# MCU.net
KiCad netlist of a schematic drawn in Altium Designer
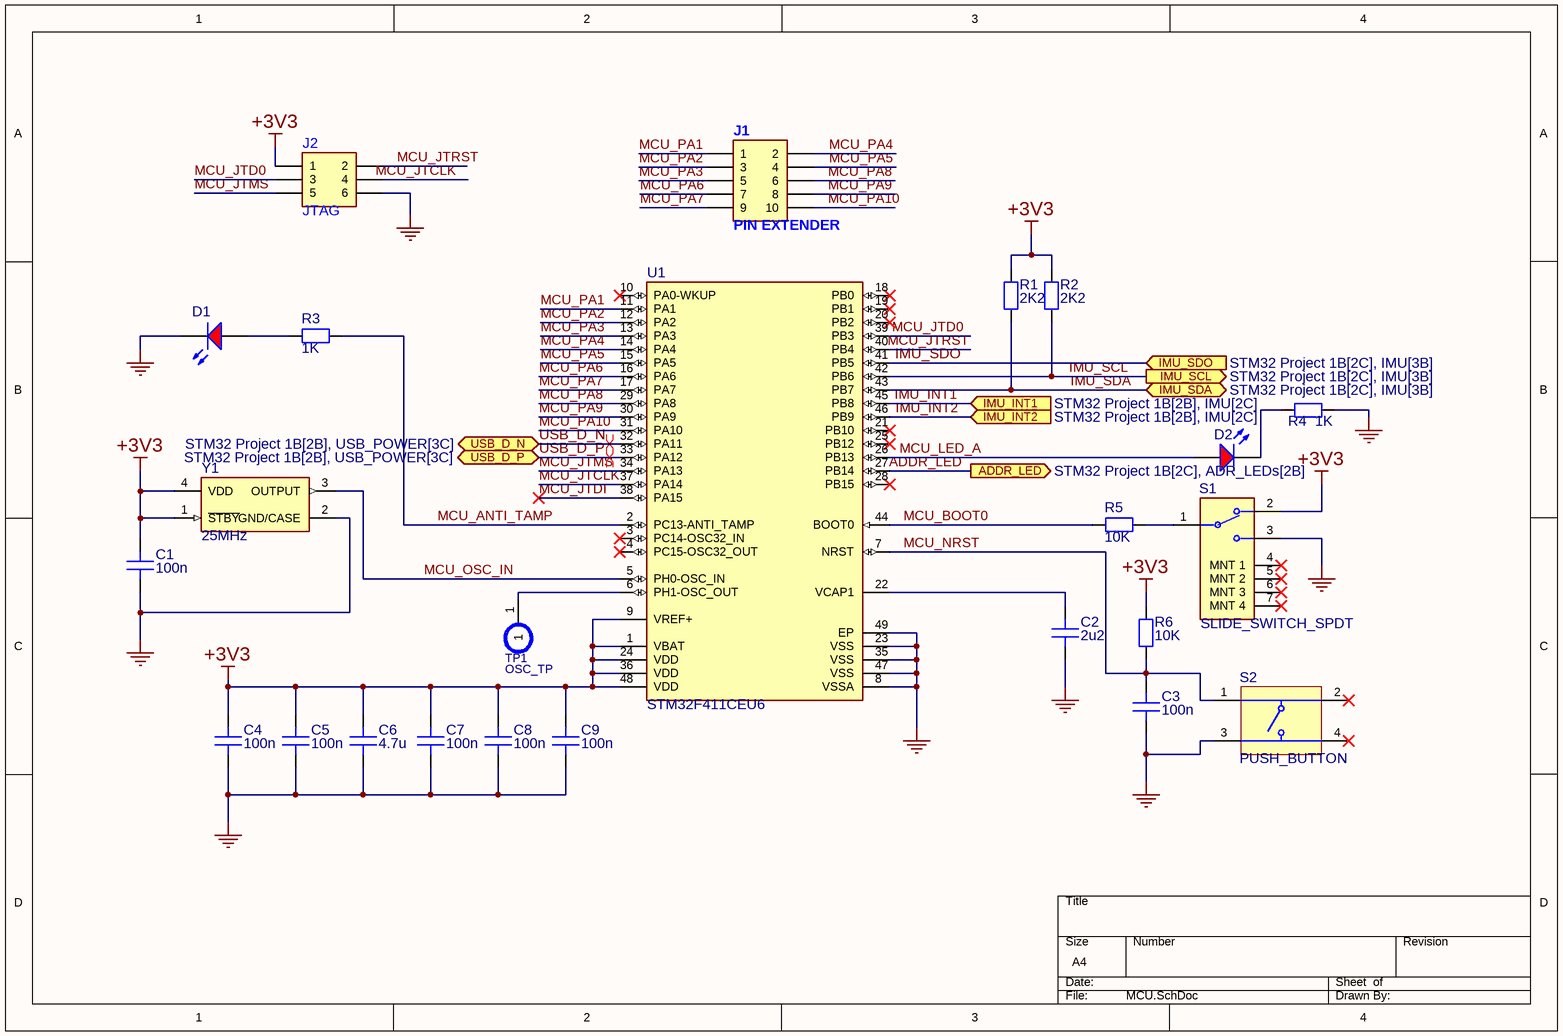
[diagram p0: MCU.SchDoc]

(export (version "E")
  (design (tool "Eeschema 10.0.6"))
  (components
    (comp (ref "C1")
      (value "100n")
      (footprint "CAP_0805")
      (description "Capacitor SMD 0805 Generic")
      (libsource (lib "Generic-Schematic-Library") (part "CAP_0805"))
    )
    (comp (ref "C2")
      (value "2u2")
      (footprint "CAP_0805")
      (description "Capacitor SMD 0805 Generic")
      (libsource (lib "Generic-Schematic-Library") (part "CAP_0805"))
    )
    (comp (ref "C3")
      (value "100n")
      (footprint "CAP_0805")
      (description "Capacitor SMD 0805 Generic")
      (libsource (lib "Generic-Schematic-Library") (part "CAP_0805"))
    )
    (comp (ref "C4")
      (value "100n")
      (footprint "CAP_0805")
      (description "Capacitor SMD 0805 Generic")
      (libsource (lib "Generic-Schematic-Library") (part "CAP_0805"))
    )
    (comp (ref "C5")
      (value "100n")
      (footprint "CAP_0805")
      (description "Capacitor SMD 0805 Generic")
      (libsource (lib "Generic-Schematic-Library") (part "CAP_0805"))
    )
    (comp (ref "C6")
      (value "4.7u")
      (footprint "CAP_0805")
      (description "Capacitor SMD 0805 Generic")
      (libsource (lib "Generic-Schematic-Library") (part "CAP_0805"))
    )
    (comp (ref "C7")
      (value "100n")
      (footprint "CAP_0805")
      (description "Capacitor SMD 0805 Generic")
      (libsource (lib "Generic-Schematic-Library") (part "CAP_0805"))
    )
    (comp (ref "C8")
      (value "100n")
      (footprint "CAP_0805")
      (description "Capacitor SMD 0805 Generic")
      (libsource (lib "Generic-Schematic-Library") (part "CAP_0805"))
    )
    (comp (ref "C9")
      (value "100n")
      (footprint "CAP_0805")
      (description "Capacitor SMD 0805 Generic")
      (libsource (lib "Generic-Schematic-Library") (part "CAP_0805"))
    )
    (comp (ref "D1")
      (value "LED_RED_0805")
      (footprint "LED_RED_0805")
      (description "Chip LED, Green, 2.2 V, -40 to 85 degC, 2-Pin SMD, Pb-Free, Tape and Reel")
      (libsource (lib "Generic-Schematic-Library") (part "LED_RED_0805"))
    )
    (comp (ref "D2")
      (value "LED_RED_0805")
      (footprint "LED_RED_0805")
      (description "Chip LED, Green, 2.2 V, -40 to 85 degC, 2-Pin SMD, Pb-Free, Tape and Reel")
      (libsource (lib "Generic-Schematic-Library") (part "LED_RED_0805"))
    )
    (comp (ref "J1")
      (value "PIN EXTENDER")
      (footprint "10P_2x5_HEADER")
      (description "10 Position SMD Pin Header 2x5")
      (libsource (lib "Generic-Schematic-Library") (part "10P_2x5_HEADER"))
    )
    (comp (ref "J2")
      (value "JTAG")
      (footprint "6P_2x3_HEADER")
      (description "Male Header, Pitch 2.54 mm, 2 x 3 Position, Height 8.13 mm, -65 to 125 degC, RoHS, Tube")
      (libsource (lib "Generic-Schematic-Library") (part "6P_2x3_HEADER"))
    )
    (comp (ref "R1")
      (value "2K2")
      (footprint "RES_0805")
      (description "Resistor SMD 0805 Generic")
      (libsource (lib "Generic-Schematic-Library") (part "RES_0805"))
    )
    (comp (ref "R2")
      (value "2K2")
      (footprint "RES_0805")
      (description "Resistor SMD 0805 Generic")
      (libsource (lib "Generic-Schematic-Library") (part "RES_0805"))
    )
    (comp (ref "R3")
      (value "1K")
      (footprint "RES_0805")
      (description "Resistor SMD 0805 Generic")
      (libsource (lib "Generic-Schematic-Library") (part "RES_0805"))
    )
    (comp (ref "R4")
      (value "1K")
      (footprint "RES_0805")
      (description "Resistor SMD 0805 Generic")
      (libsource (lib "Generic-Schematic-Library") (part "RES_0805"))
    )
    (comp (ref "R5")
      (value "10K")
      (footprint "RES_0805")
      (description "Resistor SMD 0805 Generic")
      (libsource (lib "Generic-Schematic-Library") (part "RES_0805"))
    )
    (comp (ref "R6")
      (value "10K")
      (footprint "RES_0805")
      (description "Resistor SMD 0805 Generic")
      (libsource (lib "Generic-Schematic-Library") (part "RES_0805"))
    )
    (comp (ref "S1")
      (value "SLIDE_SWITCH_SPDT")
      (footprint "SLIDE_SWITCH_SPDT")
      (description "SWITCH SLIDE SPDT 300MA 6V")
      (libsource (lib "Generic-Schematic-Library") (part "SLIDE_SWITCH_SPDT"))
    )
    (comp (ref "S2")
      (value "PUSH_BUTTON")
      (footprint "PUSH_BUTTON")
      (description "Micro Miniature Push Button Switch FSM JSM, 50 mA, -35 to 85 degC, 4-Pin SMD, RoHS, Tape and Reel")
      (fields (field (name "MANUFACTURER") "TE Connectivity"))
      (libsource (lib "Generic-Schematic-Library") (part "PUSH_BUTTON"))
    )
    (comp (ref "TP1")
      (value "OSC_TP")
      (footprint "TEST_POINT_SMD")
      (description "Test Point SMD Generic - for in circuit test")
      (libsource (lib "Generic-Schematic-Library") (part "TEST_POINT_SMD"))
    )
    (comp (ref "U1")
      (value "STM32F411CEU6")
      (footprint "STM32F411CEU6")
      (libsource (lib "Generic-Schematic-Library") (part "STM32F411CEU6"))
    )
    (comp (ref "Y1")
      (value "25MHz")
      (footprint "XTAL_OSCILLATOR_25MHz")
      (description "XTAL Oscillator 25MHz ±50ppm CMOS 3.3V 4-SMD 3.2mm x 2.5mm")
      (libsource (lib "Generic-Schematic-Library") (part "XTAL_OSCILLATOR_25MHz"))
    )
  )
  (nets
    (net (code "1") (name "+3V3") (class "Default")
      (node (ref "C1") (pin "2") (pintype "passive"))
      (node (ref "C4") (pin "2") (pintype "passive"))
      (node (ref "C5") (pin "2") (pintype "passive"))
      (node (ref "C6") (pin "2") (pintype "passive"))
      (node (ref "C7") (pin "2") (pintype "passive"))
      (node (ref "C8") (pin "2") (pintype "passive"))
      (node (ref "C9") (pin "2") (pintype "passive"))
      (node (ref "J2") (pin "1") (pinfunction "1_1") (pintype "passive"))
      (node (ref "R1") (pin "1") (pintype "passive"))
      (node (ref "R2") (pin "1") (pintype "passive"))
      (node (ref "R6") (pin "1") (pintype "passive"))
      (node (ref "S1") (pin "2") (pinfunction "2_2") (pintype "passive"))
      (node (ref "U1") (pin "1") (pinfunction "VBAT_1") (pintype "power_in"))
      (node (ref "U1") (pin "24") (pinfunction "VDD_24") (pintype "power_in"))
      (node (ref "U1") (pin "36") (pinfunction "VDD_36") (pintype "power_in"))
      (node (ref "U1") (pin "48") (pinfunction "VDD_48") (pintype "power_in"))
      (node (ref "U1") (pin "9") (pinfunction "VREF+_9") (pintype "power_in"))
      (node (ref "Y1") (pin "1") (pinfunction "~{STBY}_1") (pintype "input"))
      (node (ref "Y1") (pin "4") (pinfunction "VDD_4") (pintype "power_in"))
    )
    (net (code "2") (name "/ADDR_LED") (class "Default")
      (node (ref "U1") (pin "27") (pinfunction "PB14_27") (pintype "bidirectional"))
    )
    (net (code "3") (name "/IMU_INT1") (class "Default")
      (node (ref "U1") (pin "45") (pinfunction "PB8_45") (pintype "bidirectional"))
    )
    (net (code "4") (name "/IMU_INT2") (class "Default")
      (node (ref "U1") (pin "46") (pinfunction "PB9_46") (pintype "bidirectional"))
    )
    (net (code "5") (name "/IMU_SCL") (class "Default")
      (node (ref "R2") (pin "2") (pintype "passive"))
      (node (ref "U1") (pin "42") (pinfunction "PB6_42") (pintype "bidirectional"))
    )
    (net (code "6") (name "/IMU_SDA") (class "Default")
      (node (ref "R1") (pin "2") (pintype "passive"))
      (node (ref "U1") (pin "43") (pinfunction "PB7_43") (pintype "bidirectional"))
    )
    (net (code "7") (name "/IMU_SDO") (class "Default")
      (node (ref "U1") (pin "41") (pinfunction "PB5_41") (pintype "bidirectional"))
    )
    (net (code "8") (name "/MCU_ANTI_TAMP") (class "Default")
      (node (ref "R3") (pin "1") (pintype "passive"))
      (node (ref "U1") (pin "2") (pinfunction "PC13-ANTI_TAMP_2") (pintype "bidirectional"))
    )
    (net (code "9") (name "/MCU_BOOT0") (class "Default")
      (node (ref "R5") (pin "2") (pintype "passive"))
      (node (ref "U1") (pin "44") (pinfunction "BOOT0_44") (pintype "input"))
    )
    (net (code "10") (name "/MCU_JTCLK") (class "Default")
      (node (ref "J2") (pin "4") (pinfunction "4_4") (pintype "passive"))
      (node (ref "U1") (pin "37") (pinfunction "PA14_37") (pintype "bidirectional"))
    )
    (net (code "11") (name "/MCU_JTD0") (class "Default")
      (node (ref "J2") (pin "3") (pinfunction "3_3") (pintype "passive"))
      (node (ref "U1") (pin "39") (pinfunction "PB3_39") (pintype "bidirectional"))
    )
    (net (code "12") (name "/MCU_JTDI") (class "Default")
      (node (ref "U1") (pin "38") (pinfunction "PA15_38") (pintype "bidirectional+no_connect"))
    )
    (net (code "13") (name "/MCU_JTMS") (class "Default")
      (node (ref "J2") (pin "5") (pinfunction "5_5") (pintype "passive"))
      (node (ref "U1") (pin "34") (pinfunction "PA13_34") (pintype "bidirectional"))
    )
    (net (code "14") (name "/MCU_JTRST") (class "Default")
      (node (ref "J2") (pin "2") (pinfunction "2_2") (pintype "passive"))
      (node (ref "U1") (pin "40") (pinfunction "PB4_40") (pintype "bidirectional"))
    )
    (net (code "15") (name "/MCU_LED_A") (class "Default")
      (node (ref "D2") (pin "2") (pinfunction "A_2") (pintype "passive"))
      (node (ref "U1") (pin "26") (pinfunction "PB13_26") (pintype "bidirectional"))
    )
    (net (code "16") (name "/MCU_NRST") (class "Default")
      (node (ref "C3") (pin "2") (pintype "passive"))
      (node (ref "R6") (pin "2") (pintype "passive"))
      (node (ref "S2") (pin "1") (pinfunction "1_1") (pintype "passive"))
      (node (ref "U1") (pin "7") (pinfunction "NRST_7") (pintype "bidirectional"))
    )
    (net (code "17") (name "/MCU_OSC_IN") (class "Default")
      (node (ref "U1") (pin "5") (pinfunction "PH0-OSC_IN_5") (pintype "bidirectional"))
      (node (ref "Y1") (pin "3") (pinfunction "OUTPUT_3") (pintype "output"))
    )
    (net (code "18") (name "/MCU_PA1") (class "Default")
      (node (ref "J1") (pin "1") (pinfunction "1_1") (pintype "passive"))
      (node (ref "U1") (pin "11") (pinfunction "PA1_11") (pintype "bidirectional"))
    )
    (net (code "19") (name "/MCU_PA2") (class "Default")
      (node (ref "J1") (pin "3") (pinfunction "3_3") (pintype "passive"))
      (node (ref "U1") (pin "12") (pinfunction "PA2_12") (pintype "bidirectional"))
    )
    (net (code "20") (name "/MCU_PA3") (class "Default")
      (node (ref "J1") (pin "5") (pinfunction "5_5") (pintype "passive"))
      (node (ref "U1") (pin "13") (pinfunction "PA3_13") (pintype "bidirectional"))
    )
    (net (code "21") (name "/MCU_PA4") (class "Default")
      (node (ref "J1") (pin "2") (pinfunction "2_2") (pintype "passive"))
      (node (ref "U1") (pin "14") (pinfunction "PA4_14") (pintype "bidirectional"))
    )
    (net (code "22") (name "/MCU_PA5") (class "Default")
      (node (ref "J1") (pin "4") (pinfunction "4_4") (pintype "passive"))
      (node (ref "U1") (pin "15") (pinfunction "PA5_15") (pintype "bidirectional"))
    )
    (net (code "23") (name "/MCU_PA6") (class "Default")
      (node (ref "J1") (pin "7") (pinfunction "7_7") (pintype "passive"))
      (node (ref "U1") (pin "16") (pinfunction "PA6_16") (pintype "bidirectional"))
    )
    (net (code "24") (name "/MCU_PA7") (class "Default")
      (node (ref "J1") (pin "9") (pinfunction "9_9") (pintype "passive"))
      (node (ref "U1") (pin "17") (pinfunction "PA7_17") (pintype "bidirectional"))
    )
    (net (code "25") (name "/MCU_PA8") (class "Default")
      (node (ref "J1") (pin "6") (pinfunction "6_6") (pintype "passive"))
      (node (ref "U1") (pin "29") (pinfunction "PA8_29") (pintype "bidirectional"))
    )
    (net (code "26") (name "/MCU_PA9") (class "Default")
      (node (ref "J1") (pin "8") (pinfunction "8_8") (pintype "passive"))
      (node (ref "U1") (pin "30") (pinfunction "PA9_30") (pintype "bidirectional"))
    )
    (net (code "27") (name "/MCU_PA10") (class "Default")
      (node (ref "J1") (pin "10") (pinfunction "10_10") (pintype "passive"))
      (node (ref "U1") (pin "31") (pinfunction "PA10_31") (pintype "bidirectional"))
    )
    (net (code "28") (name "/USB_D_N") (class "Default")
      (node (ref "U1") (pin "32") (pinfunction "PA11_32") (pintype "bidirectional"))
    )
    (net (code "29") (name "/USB_D_P") (class "Default")
      (node (ref "U1") (pin "33") (pinfunction "PA12_33") (pintype "bidirectional"))
    )
    (net (code "30") (name "GND") (class "Default")
      (node (ref "C1") (pin "1") (pintype "passive"))
      (node (ref "C2") (pin "1") (pintype "passive"))
      (node (ref "C3") (pin "1") (pintype "passive"))
      (node (ref "C4") (pin "1") (pintype "passive"))
      (node (ref "C5") (pin "1") (pintype "passive"))
      (node (ref "C6") (pin "1") (pintype "passive"))
      (node (ref "C7") (pin "1") (pintype "passive"))
      (node (ref "C8") (pin "1") (pintype "passive"))
      (node (ref "C9") (pin "1") (pintype "passive"))
      (node (ref "D1") (pin "1") (pinfunction "K_1") (pintype "passive"))
      (node (ref "J2") (pin "6") (pinfunction "6_6") (pintype "passive"))
      (node (ref "R4") (pin "1") (pintype "passive"))
      (node (ref "S1") (pin "3") (pinfunction "3_3") (pintype "passive"))
      (node (ref "S2") (pin "3") (pinfunction "3_3") (pintype "passive"))
      (node (ref "U1") (pin "23") (pinfunction "VSS_23") (pintype "power_in"))
      (node (ref "U1") (pin "35") (pinfunction "VSS_35") (pintype "power_in"))
      (node (ref "U1") (pin "47") (pinfunction "VSS_47") (pintype "power_in"))
      (node (ref "U1") (pin "49") (pinfunction "EP_49") (pintype "power_in"))
      (node (ref "U1") (pin "8") (pinfunction "VSSA_8") (pintype "power_in"))
      (node (ref "Y1") (pin "2") (pinfunction "GND/CASE_2") (pintype "power_in"))
    )
    (net (code "31") (name "Net-(D1-A)") (class "Default")
      (node (ref "D1") (pin "2") (pinfunction "A_2") (pintype "passive"))
      (node (ref "R3") (pin "2") (pintype "passive"))
    )
    (net (code "32") (name "Net-(D2-K)") (class "Default")
      (node (ref "D2") (pin "1") (pinfunction "K_1") (pintype "passive"))
      (node (ref "R4") (pin "2") (pintype "passive"))
    )
    (net (code "33") (name "Net-(R5-Pad1)") (class "Default")
      (node (ref "R5") (pin "1") (pintype "passive"))
      (node (ref "S1") (pin "1") (pinfunction "1_1") (pintype "passive"))
    )
    (net (code "34") (name "Net-(U1-PH1-OSC_OUT)") (class "Default")
      (node (ref "TP1") (pin "1") (pinfunction "1_1") (pintype "passive"))
      (node (ref "U1") (pin "6") (pinfunction "PH1-OSC_OUT_6") (pintype "bidirectional"))
    )
    (net (code "35") (name "Net-(U1-VCAP1)") (class "Default")
      (node (ref "C2") (pin "2") (pintype "passive"))
      (node (ref "U1") (pin "22") (pinfunction "VCAP1_22") (pintype "passive"))
    )
    (net (code "36") (name "unconnected-(S1-MNT_1-Pad4)") (class "Default")
      (node (ref "S1") (pin "4") (pinfunction "MNT_1_4") (pintype "passive+no_connect"))
    )
    (net (code "37") (name "unconnected-(S1-MNT_2-Pad5)") (class "Default")
      (node (ref "S1") (pin "5") (pinfunction "MNT_2_5") (pintype "passive+no_connect"))
    )
    (net (code "38") (name "unconnected-(S1-MNT_3-Pad6)") (class "Default")
      (node (ref "S1") (pin "6") (pinfunction "MNT_3_6") (pintype "passive+no_connect"))
    )
    (net (code "39") (name "unconnected-(S1-MNT_4-Pad7)") (class "Default")
      (node (ref "S1") (pin "7") (pinfunction "MNT_4_7") (pintype "passive+no_connect"))
    )
    (net (code "40") (name "unconnected-(S2-Pad2)") (class "Default")
      (node (ref "S2") (pin "2") (pinfunction "2_2") (pintype "passive+no_connect"))
    )
    (net (code "41") (name "unconnected-(S2-Pad4)") (class "Default")
      (node (ref "S2") (pin "4") (pinfunction "4_4") (pintype "passive+no_connect"))
    )
    (net (code "42") (name "unconnected-(U1-PA0-WKUP-Pad10)") (class "Default")
      (node (ref "U1") (pin "10") (pinfunction "PA0-WKUP_10") (pintype "bidirectional+no_connect"))
    )
    (net (code "43") (name "unconnected-(U1-PB0-Pad18)") (class "Default")
      (node (ref "U1") (pin "18") (pinfunction "PB0_18") (pintype "bidirectional+no_connect"))
    )
    (net (code "44") (name "unconnected-(U1-PB1-Pad19)") (class "Default")
      (node (ref "U1") (pin "19") (pinfunction "PB1_19") (pintype "bidirectional+no_connect"))
    )
    (net (code "45") (name "unconnected-(U1-PB2-Pad20)") (class "Default")
      (node (ref "U1") (pin "20") (pinfunction "PB2_20") (pintype "bidirectional+no_connect"))
    )
    (net (code "46") (name "unconnected-(U1-PB10-Pad21)") (class "Default")
      (node (ref "U1") (pin "21") (pinfunction "PB10_21") (pintype "bidirectional+no_connect"))
    )
    (net (code "47") (name "unconnected-(U1-PB12-Pad25)") (class "Default")
      (node (ref "U1") (pin "25") (pinfunction "PB12_25") (pintype "bidirectional+no_connect"))
    )
    (net (code "48") (name "unconnected-(U1-PB15-Pad28)") (class "Default")
      (node (ref "U1") (pin "28") (pinfunction "PB15_28") (pintype "bidirectional+no_connect"))
    )
    (net (code "49") (name "unconnected-(U1-PC14-OSC32_IN-Pad3)") (class "Default")
      (node (ref "U1") (pin "3") (pinfunction "PC14-OSC32_IN_3") (pintype "bidirectional+no_connect"))
    )
    (net (code "50") (name "unconnected-(U1-PC15-OSC32_OUT-Pad4)") (class "Default")
      (node (ref "U1") (pin "4") (pinfunction "PC15-OSC32_OUT_4") (pintype "bidirectional+no_connect"))
    )
  )
)
